# RK3566_SDMMC.net
KiCad netlist of a schematic drawn in Altium Designer
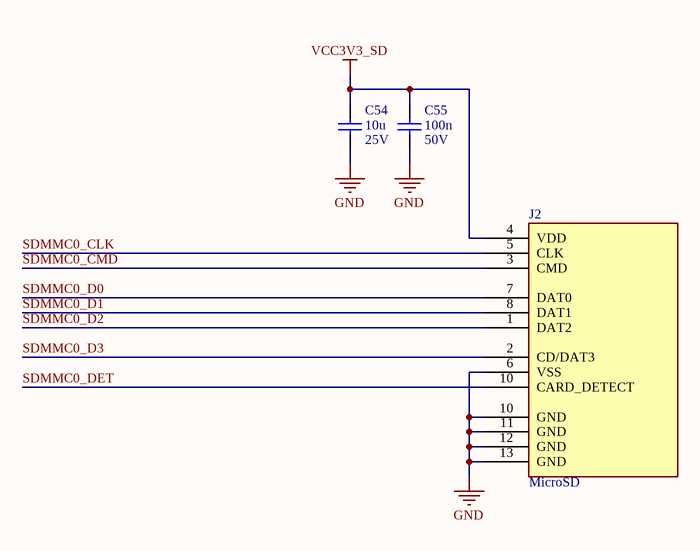
[diagram p0: RK3566_SDMMC.SchDoc]

(export (version "E")
  (design (tool "Eeschema 10.0.6"))
  (components
    (comp (ref "C54")
      (value "10u")
      (description "CAP 10U 25V X5R 0603")
      (fields (field (name "VOLTAGE") "25V") (field (name "Comment") "GRM188R61E106MA73D"))
      (libsource (lib "PersonalAltiumLibrary") (part "GRM188R61E106MA73D"))
    )
    (comp (ref "C55")
      (value "100n")
      (description "CAP 100N 50V X7R 0402")
      (fields (field (name "VOLTAGE") "50V") (field (name "Comment") "GRM155R71H104KE14D"))
      (libsource (lib "PersonalAltiumLibrary") (part "GRM155R71H104KE14D"))
    )
    (comp (ref "J2") (value "MicroSD") (libsource (lib "PersonalAltiumLibrary") (part "MicroSD")))
  )
  (nets
    (net (code "1") (name "/SDMMC0_CLK") (class "Default")
      (node (ref "J2") (pin "5") (pinfunction "CLK_5") (pintype "passive"))
    )
    (net (code "2") (name "/SDMMC0_CMD") (class "Default")
      (node (ref "J2") (pin "3") (pinfunction "CMD_3") (pintype "passive"))
    )
    (net (code "3") (name "/SDMMC0_D0") (class "Default")
      (node (ref "J2") (pin "7") (pinfunction "DAT0_7") (pintype "passive"))
    )
    (net (code "4") (name "/SDMMC0_D1") (class "Default")
      (node (ref "J2") (pin "8") (pinfunction "DAT1_8") (pintype "passive"))
    )
    (net (code "5") (name "/SDMMC0_D2") (class "Default")
      (node (ref "J2") (pin "1") (pinfunction "DAT2_1") (pintype "passive"))
    )
    (net (code "6") (name "/SDMMC0_D3") (class "Default")
      (node (ref "J2") (pin "2") (pinfunction "CD/DAT3_2") (pintype "passive"))
    )
    (net (code "7") (name "/SDMMC0_DET") (class "Default")
      (node (ref "J2") (pin "10") (pinfunction "CARD_DETECT_10") (pintype "passive"))
    )
    (net (code "8") (name "GND") (class "Default")
      (node (ref "C54") (pin "2") (pinfunction "2_2") (pintype "passive"))
      (node (ref "C55") (pin "2") (pinfunction "2_2") (pintype "passive"))
      (node (ref "J2") (pin "10") (pinfunction "GND_10") (pintype "passive"))
      (node (ref "J2") (pin "11") (pinfunction "GND_11") (pintype "passive"))
      (node (ref "J2") (pin "12") (pinfunction "GND_12") (pintype "passive"))
      (node (ref "J2") (pin "13") (pinfunction "GND_13") (pintype "passive"))
      (node (ref "J2") (pin "6") (pinfunction "VSS_6") (pintype "passive"))
    )
    (net (code "9") (name "VCC3V3_SD") (class "Default")
      (node (ref "C54") (pin "1") (pinfunction "1_1") (pintype "passive"))
      (node (ref "C55") (pin "1") (pinfunction "1_1") (pintype "passive"))
      (node (ref "J2") (pin "4") (pinfunction "VDD_4") (pintype "passive"))
    )
  )
)
